# Therm_power.net
KiCad netlist of a schematic drawn in Altium Designer
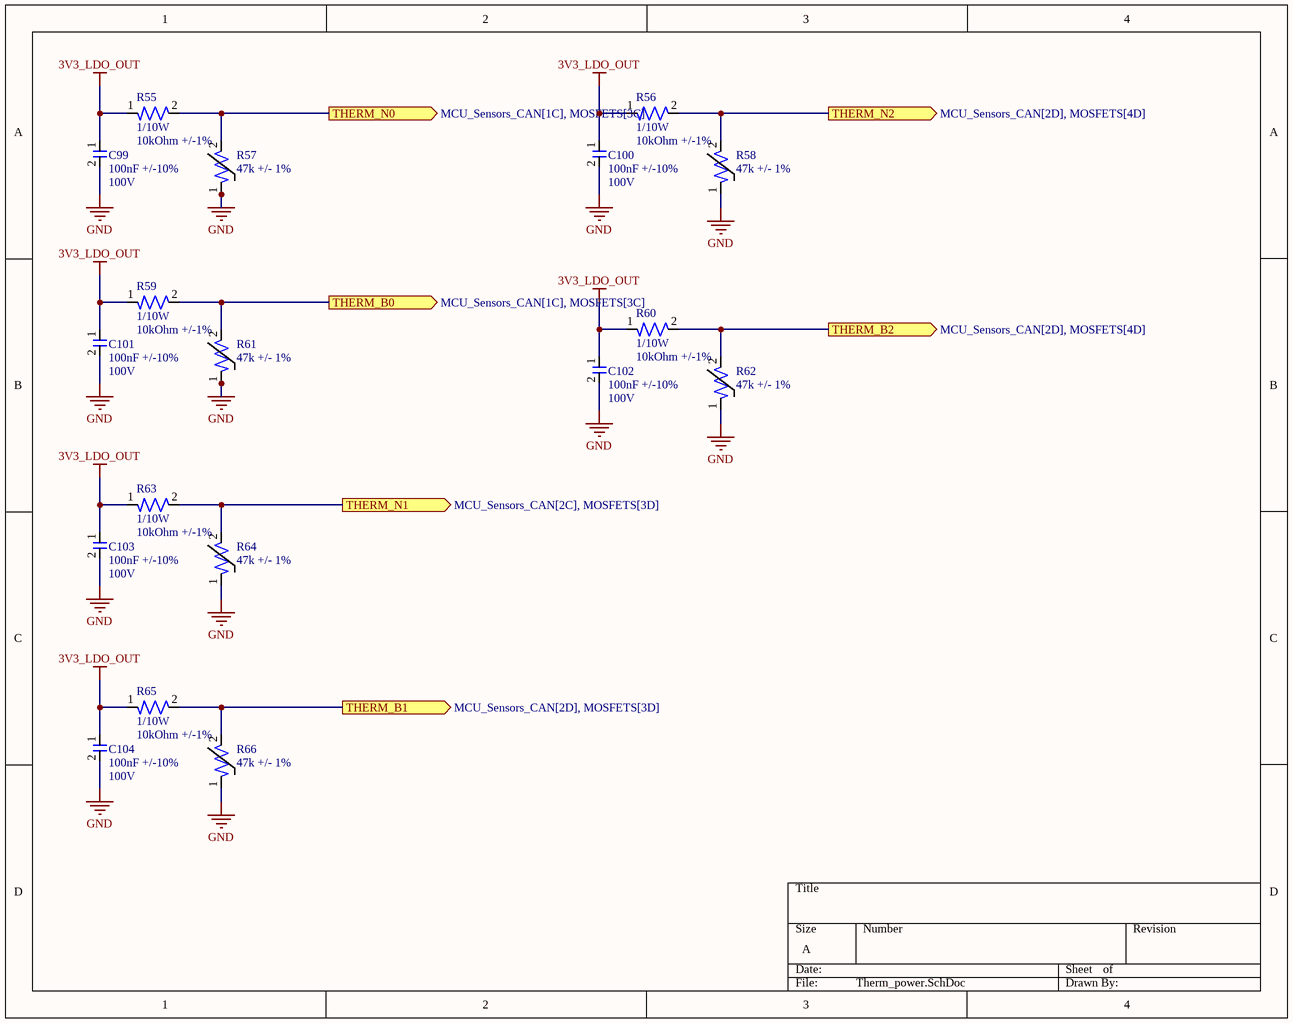
[diagram p0: Therm_power.SchDoc]

(export (version "E")
  (design (tool "Eeschema 10.0.6"))
  (components
    (comp (ref "C99")
      (value "CC0603KRX7R0BB104")
      (footprint "CAP-0603")
      (description "CAP CER 0.1UF 100V X7R 0603")
      (fields
        (field (name "MANUFACTURER") "YAGEO")
        (field (name "CAPACITANCE") "100nF +/-10%")
        (field (name "VOLTAGE RATING") "100V")
      )
      (libsource (lib "MasterLib") (part "CAP-100N-0001"))
    )
    (comp (ref "C100")
      (value "CC0603KRX7R0BB104")
      (footprint "CAP-0603")
      (description "CAP CER 0.1UF 100V X7R 0603")
      (fields
        (field (name "MANUFACTURER") "YAGEO")
        (field (name "CAPACITANCE") "100nF +/-10%")
        (field (name "VOLTAGE RATING") "100V")
      )
      (libsource (lib "MasterLib") (part "CAP-100N-0001"))
    )
    (comp (ref "C101")
      (value "CC0603KRX7R0BB104")
      (footprint "CAP-0603")
      (description "CAP CER 0.1UF 100V X7R 0603")
      (fields
        (field (name "MANUFACTURER") "YAGEO")
        (field (name "CAPACITANCE") "100nF +/-10%")
        (field (name "VOLTAGE RATING") "100V")
      )
      (libsource (lib "MasterLib") (part "CAP-100N-0001"))
    )
    (comp (ref "C102")
      (value "CC0603KRX7R0BB104")
      (footprint "CAP-0603")
      (description "CAP CER 0.1UF 100V X7R 0603")
      (fields
        (field (name "MANUFACTURER") "YAGEO")
        (field (name "CAPACITANCE") "100nF +/-10%")
        (field (name "VOLTAGE RATING") "100V")
      )
      (libsource (lib "MasterLib") (part "CAP-100N-0001"))
    )
    (comp (ref "C103")
      (value "CC0603KRX7R0BB104")
      (footprint "CAP-0603")
      (description "CAP CER 0.1UF 100V X7R 0603")
      (fields
        (field (name "MANUFACTURER") "YAGEO")
        (field (name "CAPACITANCE") "100nF +/-10%")
        (field (name "VOLTAGE RATING") "100V")
      )
      (libsource (lib "MasterLib") (part "CAP-100N-0001"))
    )
    (comp (ref "C104")
      (value "CC0603KRX7R0BB104")
      (footprint "CAP-0603")
      (description "CAP CER 0.1UF 100V X7R 0603")
      (fields
        (field (name "MANUFACTURER") "YAGEO")
        (field (name "CAPACITANCE") "100nF +/-10%")
        (field (name "VOLTAGE RATING") "100V")
      )
      (libsource (lib "MasterLib") (part "CAP-100N-0001"))
    )
    (comp (ref "R55")
      (value "RC0603FR-0710KP")
      (footprint "RES-0603")
      (description "RES SMD 10K OHM 1% 1/10W 0603")
      (fields
        (field (name "MANUFACTURER") "YAGEO")
        (field (name "POWER RATING") "1/10W")
        (field (name "RESISTANCE") "10kOhm +/-1%")
      )
      (libsource (lib "MasterLib") (part "RES-10K-0002"))
    )
    (comp (ref "R56")
      (value "RC0603FR-0710KP")
      (footprint "RES-0603")
      (description "RES SMD 10K OHM 1% 1/10W 0603")
      (fields
        (field (name "MANUFACTURER") "YAGEO")
        (field (name "POWER RATING") "1/10W")
        (field (name "RESISTANCE") "10kOhm +/-1%")
      )
      (libsource (lib "MasterLib") (part "RES-10K-0002"))
    )
    (comp (ref "R57")
      (value "TMP6431DECR")
      (footprint "RES-0402")
      (description "PTC Thermistor 47 kOhms 0402 (1006 Metric)")
      (fields (field (name "MANUFACTURER") "Texas Instruments") (field (name "RESISTANCE") "47k +/- 1%"))
      (libsource (lib "MasterLib") (part "THERM-47K-0001"))
    )
    (comp (ref "R58")
      (value "TMP6431DECR")
      (footprint "RES-0402")
      (description "PTC Thermistor 47 kOhms 0402 (1006 Metric)")
      (fields (field (name "MANUFACTURER") "Texas Instruments") (field (name "RESISTANCE") "47k +/- 1%"))
      (libsource (lib "MasterLib") (part "THERM-47K-0001"))
    )
    (comp (ref "R59")
      (value "RC0603FR-0710KP")
      (footprint "RES-0603")
      (description "RES SMD 10K OHM 1% 1/10W 0603")
      (fields
        (field (name "MANUFACTURER") "YAGEO")
        (field (name "POWER RATING") "1/10W")
        (field (name "RESISTANCE") "10kOhm +/-1%")
      )
      (libsource (lib "MasterLib") (part "RES-10K-0002"))
    )
    (comp (ref "R60")
      (value "RC0603FR-0710KP")
      (footprint "RES-0603")
      (description "RES SMD 10K OHM 1% 1/10W 0603")
      (fields
        (field (name "MANUFACTURER") "YAGEO")
        (field (name "POWER RATING") "1/10W")
        (field (name "RESISTANCE") "10kOhm +/-1%")
      )
      (libsource (lib "MasterLib") (part "RES-10K-0002"))
    )
    (comp (ref "R61")
      (value "TMP6431DECR")
      (footprint "RES-0402")
      (description "PTC Thermistor 47 kOhms 0402 (1006 Metric)")
      (fields (field (name "MANUFACTURER") "Texas Instruments") (field (name "RESISTANCE") "47k +/- 1%"))
      (libsource (lib "MasterLib") (part "THERM-47K-0001"))
    )
    (comp (ref "R62")
      (value "TMP6431DECR")
      (footprint "RES-0402")
      (description "PTC Thermistor 47 kOhms 0402 (1006 Metric)")
      (fields (field (name "MANUFACTURER") "Texas Instruments") (field (name "RESISTANCE") "47k +/- 1%"))
      (libsource (lib "MasterLib") (part "THERM-47K-0001"))
    )
    (comp (ref "R63")
      (value "RC0603FR-0710KP")
      (footprint "RES-0603")
      (description "RES SMD 10K OHM 1% 1/10W 0603")
      (fields
        (field (name "MANUFACTURER") "YAGEO")
        (field (name "POWER RATING") "1/10W")
        (field (name "RESISTANCE") "10kOhm +/-1%")
      )
      (libsource (lib "MasterLib") (part "RES-10K-0002"))
    )
    (comp (ref "R64")
      (value "TMP6431DECR")
      (footprint "RES-0402")
      (description "PTC Thermistor 47 kOhms 0402 (1006 Metric)")
      (fields (field (name "MANUFACTURER") "Texas Instruments") (field (name "RESISTANCE") "47k +/- 1%"))
      (libsource (lib "MasterLib") (part "THERM-47K-0001"))
    )
    (comp (ref "R65")
      (value "RC0603FR-0710KP")
      (footprint "RES-0603")
      (description "RES SMD 10K OHM 1% 1/10W 0603")
      (fields
        (field (name "MANUFACTURER") "YAGEO")
        (field (name "POWER RATING") "1/10W")
        (field (name "RESISTANCE") "10kOhm +/-1%")
      )
      (libsource (lib "MasterLib") (part "RES-10K-0002"))
    )
    (comp (ref "R66")
      (value "TMP6431DECR")
      (footprint "RES-0402")
      (description "PTC Thermistor 47 kOhms 0402 (1006 Metric)")
      (fields (field (name "MANUFACTURER") "Texas Instruments") (field (name "RESISTANCE") "47k +/- 1%"))
      (libsource (lib "MasterLib") (part "THERM-47K-0001"))
    )
  )
  (nets
    (net (code "1") (name "/THERM_B0") (class "Default")
      (node (ref "R59") (pin "2") (pinfunction "2_2") (pintype "passive"))
      (node (ref "R61") (pin "2") (pinfunction "2_2") (pintype "passive"))
    )
    (net (code "2") (name "/THERM_B1") (class "Default")
      (node (ref "R65") (pin "2") (pinfunction "2_2") (pintype "passive"))
      (node (ref "R66") (pin "2") (pinfunction "2_2") (pintype "passive"))
    )
    (net (code "3") (name "/THERM_B2") (class "Default")
      (node (ref "R60") (pin "2") (pinfunction "2_2") (pintype "passive"))
      (node (ref "R62") (pin "2") (pinfunction "2_2") (pintype "passive"))
    )
    (net (code "4") (name "/THERM_N0") (class "Default")
      (node (ref "R55") (pin "2") (pinfunction "2_2") (pintype "passive"))
      (node (ref "R57") (pin "2") (pinfunction "2_2") (pintype "passive"))
    )
    (net (code "5") (name "/THERM_N1") (class "Default")
      (node (ref "R63") (pin "2") (pinfunction "2_2") (pintype "passive"))
      (node (ref "R64") (pin "2") (pinfunction "2_2") (pintype "passive"))
    )
    (net (code "6") (name "/THERM_N2") (class "Default")
      (node (ref "R56") (pin "2") (pinfunction "2_2") (pintype "passive"))
      (node (ref "R58") (pin "2") (pinfunction "2_2") (pintype "passive"))
    )
    (net (code "7") (name "3V3_LDO_OUT") (class "Default")
      (node (ref "C100") (pin "1") (pinfunction "1_1") (pintype "passive"))
      (node (ref "C101") (pin "1") (pinfunction "1_1") (pintype "passive"))
      (node (ref "C102") (pin "1") (pinfunction "1_1") (pintype "passive"))
      (node (ref "C103") (pin "1") (pinfunction "1_1") (pintype "passive"))
      (node (ref "C104") (pin "1") (pinfunction "1_1") (pintype "passive"))
      (node (ref "C99") (pin "1") (pinfunction "1_1") (pintype "passive"))
      (node (ref "R55") (pin "1") (pinfunction "1_1") (pintype "passive"))
      (node (ref "R56") (pin "1") (pinfunction "1_1") (pintype "passive"))
      (node (ref "R59") (pin "1") (pinfunction "1_1") (pintype "passive"))
      (node (ref "R60") (pin "1") (pinfunction "1_1") (pintype "passive"))
      (node (ref "R63") (pin "1") (pinfunction "1_1") (pintype "passive"))
      (node (ref "R65") (pin "1") (pinfunction "1_1") (pintype "passive"))
    )
    (net (code "8") (name "GND") (class "Default")
      (node (ref "C100") (pin "2") (pinfunction "2_2") (pintype "passive"))
      (node (ref "C101") (pin "2") (pinfunction "2_2") (pintype "passive"))
      (node (ref "C102") (pin "2") (pinfunction "2_2") (pintype "passive"))
      (node (ref "C103") (pin "2") (pinfunction "2_2") (pintype "passive"))
      (node (ref "C104") (pin "2") (pinfunction "2_2") (pintype "passive"))
      (node (ref "C99") (pin "2") (pinfunction "2_2") (pintype "passive"))
      (node (ref "R57") (pin "1") (pinfunction "1_1") (pintype "passive"))
      (node (ref "R58") (pin "1") (pinfunction "1_1") (pintype "passive"))
      (node (ref "R61") (pin "1") (pinfunction "1_1") (pintype "passive"))
      (node (ref "R62") (pin "1") (pinfunction "1_1") (pintype "passive"))
      (node (ref "R64") (pin "1") (pinfunction "1_1") (pintype "passive"))
      (node (ref "R66") (pin "1") (pinfunction "1_1") (pintype "passive"))
    )
  )
)
